# SuperClock_LED.net
KiCad netlist of a schematic drawn in Altium Designer
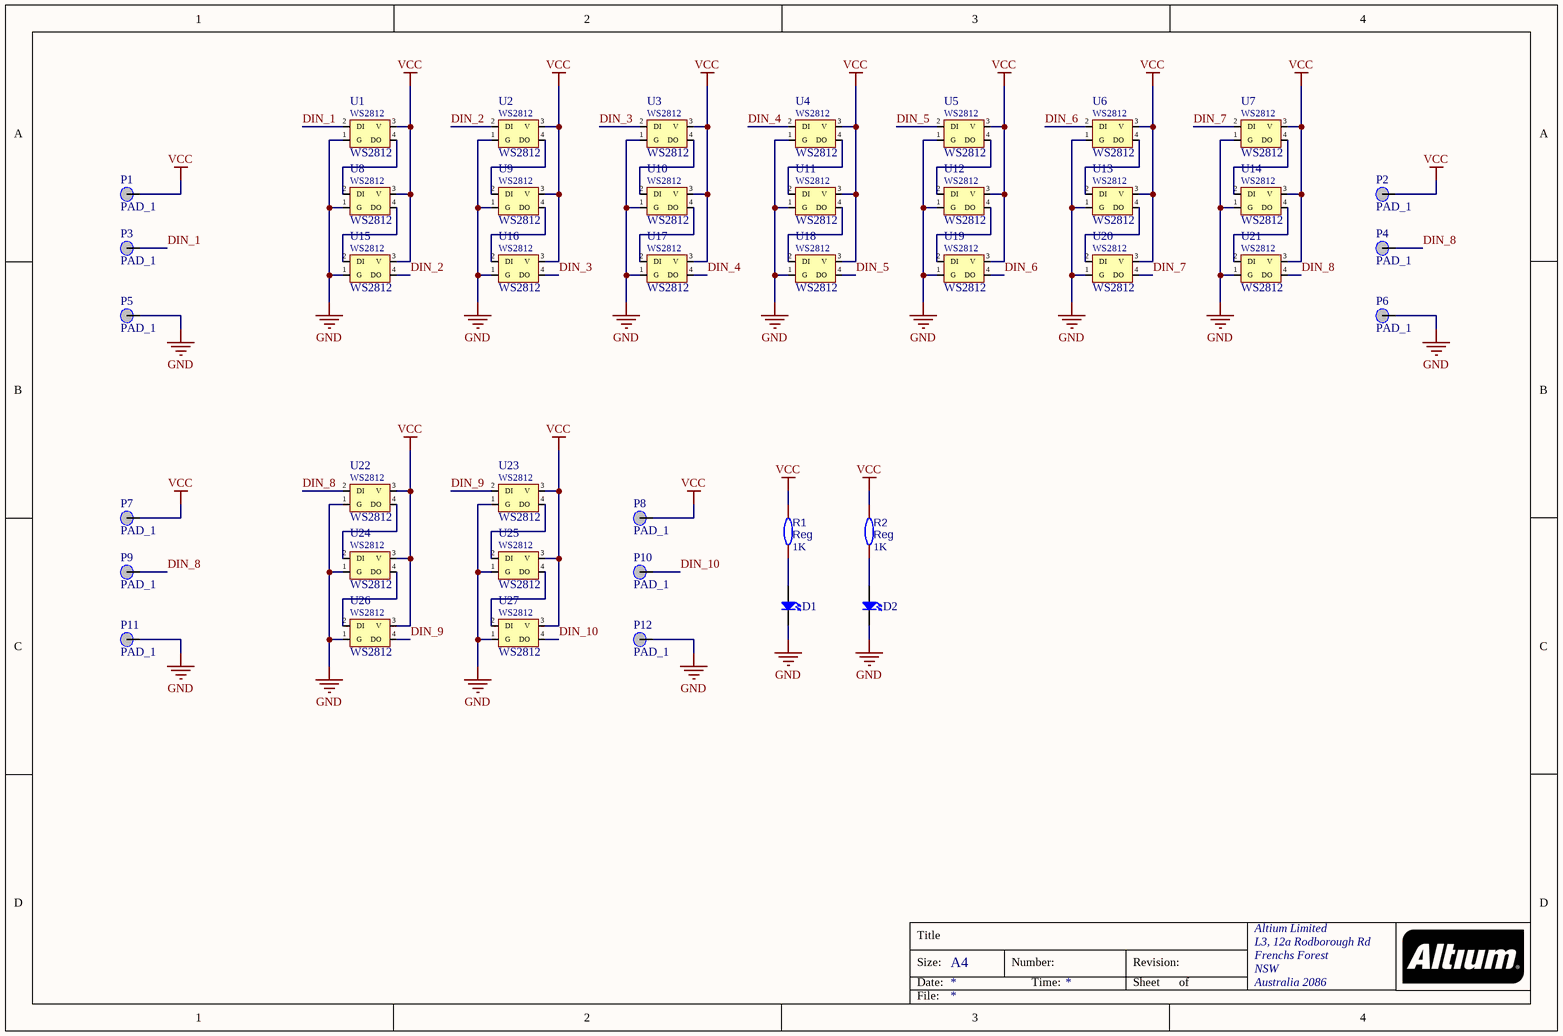
[diagram p0: SuperClock_LED.SchDoc]

(export (version "E")
  (design (tool "Eeschema 10.0.6"))
  (components
    (comp (ref "D1")
      (value "LED")
      (footprint "LED0603")
      (fields (field (name "PUBLISHER") "Altium Limited"))
      (libsource (lib "Levent_lib") (part "LED0"))
    )
    (comp (ref "D2")
      (value "LED")
      (footprint "LED0603")
      (fields (field (name "PUBLISHER") "Altium Limited"))
      (libsource (lib "Levent_lib") (part "LED0"))
    )
    (comp (ref "P1")
      (value "PAD_1")
      (footprint "PAD_PIN_1_SMD_ARC")
      (description "1脚焊盘")
      (libsource (lib "Levent_lib") (part "PAD_1"))
    )
    (comp (ref "P2")
      (value "PAD_1")
      (footprint "PAD_PIN_1_SMD_ARC")
      (description "1脚焊盘")
      (libsource (lib "Levent_lib") (part "PAD_1"))
    )
    (comp (ref "P3")
      (value "PAD_1")
      (footprint "PAD_PIN_1_SMD_ARC")
      (description "1脚焊盘")
      (libsource (lib "Levent_lib") (part "PAD_1"))
    )
    (comp (ref "P4")
      (value "PAD_1")
      (footprint "PAD_PIN_1_SMD_ARC")
      (description "1脚焊盘")
      (libsource (lib "Levent_lib") (part "PAD_1"))
    )
    (comp (ref "P5")
      (value "PAD_1")
      (footprint "PAD_PIN_1_SMD_ARC")
      (description "1脚焊盘")
      (libsource (lib "Levent_lib") (part "PAD_1"))
    )
    (comp (ref "P6")
      (value "PAD_1")
      (footprint "PAD_PIN_1_SMD_ARC")
      (description "1脚焊盘")
      (libsource (lib "Levent_lib") (part "PAD_1"))
    )
    (comp (ref "P7")
      (value "PAD_1")
      (footprint "PAD_PIN_1_SMD_ARC")
      (description "1脚焊盘")
      (libsource (lib "Levent_lib") (part "PAD_1"))
    )
    (comp (ref "P8")
      (value "PAD_1")
      (footprint "PAD_PIN_1_SMD_ARC")
      (description "1脚焊盘")
      (libsource (lib "Levent_lib") (part "PAD_1"))
    )
    (comp (ref "P9")
      (value "PAD_1")
      (footprint "PAD_PIN_1_SMD_ARC")
      (description "1脚焊盘")
      (libsource (lib "Levent_lib") (part "PAD_1"))
    )
    (comp (ref "P10")
      (value "PAD_1")
      (footprint "PAD_PIN_1_SMD_ARC")
      (description "1脚焊盘")
      (libsource (lib "Levent_lib") (part "PAD_1"))
    )
    (comp (ref "P11")
      (value "PAD_1")
      (footprint "PAD_PIN_1_SMD_ARC")
      (description "1脚焊盘")
      (libsource (lib "Levent_lib") (part "PAD_1"))
    )
    (comp (ref "P12")
      (value "PAD_1")
      (footprint "PAD_PIN_1_SMD_ARC")
      (description "1脚焊盘")
      (libsource (lib "Levent_lib") (part "PAD_1"))
    )
    (comp (ref "R1")
      (value "Reg")
      (footprint "R0603")
      (description "电阻")
      (fields
        (field (name "BOM_SUPPLIER PART") "C465721")
        (field (name "BOM_MANUFACTURER PART") "AR03BTCX1002A")
        (field (name "ALTIUM_VALUE") "1K")
        (field (name "CONTRIBUTOR") "LCSC")
      )
      (libsource (lib "Levent_lib") (part "Res"))
    )
    (comp (ref "R2")
      (value "Reg")
      (footprint "R0603")
      (description "电阻")
      (fields
        (field (name "BOM_SUPPLIER PART") "C465721")
        (field (name "BOM_MANUFACTURER PART") "AR03BTCX1002A")
        (field (name "ALTIUM_VALUE") "1K")
        (field (name "CONTRIBUTOR") "LCSC")
      )
      (libsource (lib "Levent_lib") (part "Res"))
    )
    (comp (ref "U1")
      (value "WS2812")
      (footprint "WS2812B-2020")
      (description "WS2812全色LED")
      (libsource (lib "Levent_lib") (part "WS2812"))
    )
    (comp (ref "U2")
      (value "WS2812")
      (footprint "WS2812B-2020")
      (description "WS2812全色LED")
      (libsource (lib "Levent_lib") (part "WS2812"))
    )
    (comp (ref "U3")
      (value "WS2812")
      (footprint "WS2812B-2020")
      (description "WS2812全色LED")
      (libsource (lib "Levent_lib") (part "WS2812"))
    )
    (comp (ref "U4")
      (value "WS2812")
      (footprint "WS2812B-2020")
      (description "WS2812全色LED")
      (libsource (lib "Levent_lib") (part "WS2812"))
    )
    (comp (ref "U5")
      (value "WS2812")
      (footprint "WS2812B-2020")
      (description "WS2812全色LED")
      (libsource (lib "Levent_lib") (part "WS2812"))
    )
    (comp (ref "U6")
      (value "WS2812")
      (footprint "WS2812B-2020")
      (description "WS2812全色LED")
      (libsource (lib "Levent_lib") (part "WS2812"))
    )
    (comp (ref "U7")
      (value "WS2812")
      (footprint "WS2812B-2020")
      (description "WS2812全色LED")
      (libsource (lib "Levent_lib") (part "WS2812"))
    )
    (comp (ref "U8")
      (value "WS2812")
      (footprint "WS2812B-2020")
      (description "WS2812全色LED")
      (libsource (lib "Levent_lib") (part "WS2812"))
    )
    (comp (ref "U9")
      (value "WS2812")
      (footprint "WS2812B-2020")
      (description "WS2812全色LED")
      (libsource (lib "Levent_lib") (part "WS2812"))
    )
    (comp (ref "U10")
      (value "WS2812")
      (footprint "WS2812B-2020")
      (description "WS2812全色LED")
      (libsource (lib "Levent_lib") (part "WS2812"))
    )
    (comp (ref "U11")
      (value "WS2812")
      (footprint "WS2812B-2020")
      (description "WS2812全色LED")
      (libsource (lib "Levent_lib") (part "WS2812"))
    )
    (comp (ref "U12")
      (value "WS2812")
      (footprint "WS2812B-2020")
      (description "WS2812全色LED")
      (libsource (lib "Levent_lib") (part "WS2812"))
    )
    (comp (ref "U13")
      (value "WS2812")
      (footprint "WS2812B-2020")
      (description "WS2812全色LED")
      (libsource (lib "Levent_lib") (part "WS2812"))
    )
    (comp (ref "U14")
      (value "WS2812")
      (footprint "WS2812B-2020")
      (description "WS2812全色LED")
      (libsource (lib "Levent_lib") (part "WS2812"))
    )
    (comp (ref "U15")
      (value "WS2812")
      (footprint "WS2812B-2020")
      (description "WS2812全色LED")
      (libsource (lib "Levent_lib") (part "WS2812"))
    )
    (comp (ref "U16")
      (value "WS2812")
      (footprint "WS2812B-2020")
      (description "WS2812全色LED")
      (libsource (lib "Levent_lib") (part "WS2812"))
    )
    (comp (ref "U17")
      (value "WS2812")
      (footprint "WS2812B-2020")
      (description "WS2812全色LED")
      (libsource (lib "Levent_lib") (part "WS2812"))
    )
    (comp (ref "U18")
      (value "WS2812")
      (footprint "WS2812B-2020")
      (description "WS2812全色LED")
      (libsource (lib "Levent_lib") (part "WS2812"))
    )
    (comp (ref "U19")
      (value "WS2812")
      (footprint "WS2812B-2020")
      (description "WS2812全色LED")
      (libsource (lib "Levent_lib") (part "WS2812"))
    )
    (comp (ref "U20")
      (value "WS2812")
      (footprint "WS2812B-2020")
      (description "WS2812全色LED")
      (libsource (lib "Levent_lib") (part "WS2812"))
    )
    (comp (ref "U21")
      (value "WS2812")
      (footprint "WS2812B-2020")
      (description "WS2812全色LED")
      (libsource (lib "Levent_lib") (part "WS2812"))
    )
    (comp (ref "U22")
      (value "WS2812")
      (footprint "WS2812B-2020")
      (description "WS2812全色LED")
      (libsource (lib "Levent_lib") (part "WS2812"))
    )
    (comp (ref "U23")
      (value "WS2812")
      (footprint "WS2812B-2020")
      (description "WS2812全色LED")
      (libsource (lib "Levent_lib") (part "WS2812"))
    )
    (comp (ref "U24")
      (value "WS2812")
      (footprint "WS2812B-2020")
      (description "WS2812全色LED")
      (libsource (lib "Levent_lib") (part "WS2812"))
    )
    (comp (ref "U25")
      (value "WS2812")
      (footprint "WS2812B-2020")
      (description "WS2812全色LED")
      (libsource (lib "Levent_lib") (part "WS2812"))
    )
    (comp (ref "U26")
      (value "WS2812")
      (footprint "WS2812B-2020")
      (description "WS2812全色LED")
      (libsource (lib "Levent_lib") (part "WS2812"))
    )
    (comp (ref "U27")
      (value "WS2812")
      (footprint "WS2812B-2020")
      (description "WS2812全色LED")
      (libsource (lib "Levent_lib") (part "WS2812"))
    )
  )
  (nets
    (net (code "1") (name "/DIN_1") (class "Default")
      (node (ref "P3") (pin "1") (pinfunction "1_1") (pintype "passive"))
      (node (ref "U1") (pin "2") (pinfunction "DI_2") (pintype "passive"))
    )
    (net (code "2") (name "/DIN_2") (class "Default")
      (node (ref "U15") (pin "4") (pinfunction "DO_4") (pintype "passive"))
      (node (ref "U2") (pin "2") (pinfunction "DI_2") (pintype "passive"))
    )
    (net (code "3") (name "/DIN_3") (class "Default")
      (node (ref "U16") (pin "4") (pinfunction "DO_4") (pintype "passive"))
      (node (ref "U3") (pin "2") (pinfunction "DI_2") (pintype "passive"))
    )
    (net (code "4") (name "/DIN_4") (class "Default")
      (node (ref "U17") (pin "4") (pinfunction "DO_4") (pintype "passive"))
      (node (ref "U4") (pin "2") (pinfunction "DI_2") (pintype "passive"))
    )
    (net (code "5") (name "/DIN_5") (class "Default")
      (node (ref "U18") (pin "4") (pinfunction "DO_4") (pintype "passive"))
      (node (ref "U5") (pin "2") (pinfunction "DI_2") (pintype "passive"))
    )
    (net (code "6") (name "/DIN_6") (class "Default")
      (node (ref "U19") (pin "4") (pinfunction "DO_4") (pintype "passive"))
      (node (ref "U6") (pin "2") (pinfunction "DI_2") (pintype "passive"))
    )
    (net (code "7") (name "/DIN_7") (class "Default")
      (node (ref "U20") (pin "4") (pinfunction "DO_4") (pintype "passive"))
      (node (ref "U7") (pin "2") (pinfunction "DI_2") (pintype "passive"))
    )
    (net (code "8") (name "/DIN_8") (class "Default")
      (node (ref "P4") (pin "1") (pinfunction "1_1") (pintype "passive"))
      (node (ref "P9") (pin "1") (pinfunction "1_1") (pintype "passive"))
      (node (ref "U21") (pin "4") (pinfunction "DO_4") (pintype "passive"))
      (node (ref "U22") (pin "2") (pinfunction "DI_2") (pintype "passive"))
    )
    (net (code "9") (name "/DIN_9") (class "Default")
      (node (ref "U23") (pin "2") (pinfunction "DI_2") (pintype "passive"))
      (node (ref "U26") (pin "4") (pinfunction "DO_4") (pintype "passive"))
    )
    (net (code "10") (name "/DIN_10") (class "Default")
      (node (ref "P10") (pin "1") (pinfunction "1_1") (pintype "passive"))
      (node (ref "U27") (pin "4") (pinfunction "DO_4") (pintype "passive"))
    )
    (net (code "11") (name "GND") (class "Default")
      (node (ref "D1") (pin "1") (pinfunction "K_1") (pintype "passive"))
      (node (ref "D2") (pin "1") (pinfunction "K_1") (pintype "passive"))
      (node (ref "P11") (pin "1") (pinfunction "1_1") (pintype "passive"))
      (node (ref "P12") (pin "1") (pinfunction "1_1") (pintype "passive"))
      (node (ref "P5") (pin "1") (pinfunction "1_1") (pintype "passive"))
      (node (ref "P6") (pin "1") (pinfunction "1_1") (pintype "passive"))
      (node (ref "U1") (pin "1") (pinfunction "G_1") (pintype "passive"))
      (node (ref "U10") (pin "1") (pinfunction "G_1") (pintype "passive"))
      (node (ref "U11") (pin "1") (pinfunction "G_1") (pintype "passive"))
      (node (ref "U12") (pin "1") (pinfunction "G_1") (pintype "passive"))
      (node (ref "U13") (pin "1") (pinfunction "G_1") (pintype "passive"))
      (node (ref "U14") (pin "1") (pinfunction "G_1") (pintype "passive"))
      (node (ref "U15") (pin "1") (pinfunction "G_1") (pintype "passive"))
      (node (ref "U16") (pin "1") (pinfunction "G_1") (pintype "passive"))
      (node (ref "U17") (pin "1") (pinfunction "G_1") (pintype "passive"))
      (node (ref "U18") (pin "1") (pinfunction "G_1") (pintype "passive"))
      (node (ref "U19") (pin "1") (pinfunction "G_1") (pintype "passive"))
      (node (ref "U2") (pin "1") (pinfunction "G_1") (pintype "passive"))
      (node (ref "U20") (pin "1") (pinfunction "G_1") (pintype "passive"))
      (node (ref "U21") (pin "1") (pinfunction "G_1") (pintype "passive"))
      (node (ref "U22") (pin "1") (pinfunction "G_1") (pintype "passive"))
      (node (ref "U23") (pin "1") (pinfunction "G_1") (pintype "passive"))
      (node (ref "U24") (pin "1") (pinfunction "G_1") (pintype "passive"))
      (node (ref "U25") (pin "1") (pinfunction "G_1") (pintype "passive"))
      (node (ref "U26") (pin "1") (pinfunction "G_1") (pintype "passive"))
      (node (ref "U27") (pin "1") (pinfunction "G_1") (pintype "passive"))
      (node (ref "U3") (pin "1") (pinfunction "G_1") (pintype "passive"))
      (node (ref "U4") (pin "1") (pinfunction "G_1") (pintype "passive"))
      (node (ref "U5") (pin "1") (pinfunction "G_1") (pintype "passive"))
      (node (ref "U6") (pin "1") (pinfunction "G_1") (pintype "passive"))
      (node (ref "U7") (pin "1") (pinfunction "G_1") (pintype "passive"))
      (node (ref "U8") (pin "1") (pinfunction "G_1") (pintype "passive"))
      (node (ref "U9") (pin "1") (pinfunction "G_1") (pintype "passive"))
    )
    (net (code "12") (name "Net-(D1-A)") (class "Default")
      (node (ref "D1") (pin "2") (pinfunction "A_2") (pintype "passive"))
      (node (ref "R1") (pin "1") (pinfunction "1_1") (pintype "passive"))
    )
    (net (code "13") (name "Net-(D2-A)") (class "Default")
      (node (ref "D2") (pin "2") (pinfunction "A_2") (pintype "passive"))
      (node (ref "R2") (pin "1") (pinfunction "1_1") (pintype "passive"))
    )
    (net (code "14") (name "Net-(U1-DO)") (class "Default")
      (node (ref "U1") (pin "4") (pinfunction "DO_4") (pintype "passive"))
      (node (ref "U8") (pin "2") (pinfunction "DI_2") (pintype "passive"))
    )
    (net (code "15") (name "Net-(U2-DO)") (class "Default")
      (node (ref "U2") (pin "4") (pinfunction "DO_4") (pintype "passive"))
      (node (ref "U9") (pin "2") (pinfunction "DI_2") (pintype "passive"))
    )
    (net (code "16") (name "Net-(U10-DI)") (class "Default")
      (node (ref "U10") (pin "2") (pinfunction "DI_2") (pintype "passive"))
      (node (ref "U3") (pin "4") (pinfunction "DO_4") (pintype "passive"))
    )
    (net (code "17") (name "Net-(U10-DO)") (class "Default")
      (node (ref "U10") (pin "4") (pinfunction "DO_4") (pintype "passive"))
      (node (ref "U17") (pin "2") (pinfunction "DI_2") (pintype "passive"))
    )
    (net (code "18") (name "Net-(U11-DI)") (class "Default")
      (node (ref "U11") (pin "2") (pinfunction "DI_2") (pintype "passive"))
      (node (ref "U4") (pin "4") (pinfunction "DO_4") (pintype "passive"))
    )
    (net (code "19") (name "Net-(U11-DO)") (class "Default")
      (node (ref "U11") (pin "4") (pinfunction "DO_4") (pintype "passive"))
      (node (ref "U18") (pin "2") (pinfunction "DI_2") (pintype "passive"))
    )
    (net (code "20") (name "Net-(U12-DI)") (class "Default")
      (node (ref "U12") (pin "2") (pinfunction "DI_2") (pintype "passive"))
      (node (ref "U5") (pin "4") (pinfunction "DO_4") (pintype "passive"))
    )
    (net (code "21") (name "Net-(U12-DO)") (class "Default")
      (node (ref "U12") (pin "4") (pinfunction "DO_4") (pintype "passive"))
      (node (ref "U19") (pin "2") (pinfunction "DI_2") (pintype "passive"))
    )
    (net (code "22") (name "Net-(U13-DI)") (class "Default")
      (node (ref "U13") (pin "2") (pinfunction "DI_2") (pintype "passive"))
      (node (ref "U6") (pin "4") (pinfunction "DO_4") (pintype "passive"))
    )
    (net (code "23") (name "Net-(U13-DO)") (class "Default")
      (node (ref "U13") (pin "4") (pinfunction "DO_4") (pintype "passive"))
      (node (ref "U20") (pin "2") (pinfunction "DI_2") (pintype "passive"))
    )
    (net (code "24") (name "Net-(U14-DI)") (class "Default")
      (node (ref "U14") (pin "2") (pinfunction "DI_2") (pintype "passive"))
      (node (ref "U7") (pin "4") (pinfunction "DO_4") (pintype "passive"))
    )
    (net (code "25") (name "Net-(U14-DO)") (class "Default")
      (node (ref "U14") (pin "4") (pinfunction "DO_4") (pintype "passive"))
      (node (ref "U21") (pin "2") (pinfunction "DI_2") (pintype "passive"))
    )
    (net (code "26") (name "Net-(U15-DI)") (class "Default")
      (node (ref "U15") (pin "2") (pinfunction "DI_2") (pintype "passive"))
      (node (ref "U8") (pin "4") (pinfunction "DO_4") (pintype "passive"))
    )
    (net (code "27") (name "Net-(U16-DI)") (class "Default")
      (node (ref "U16") (pin "2") (pinfunction "DI_2") (pintype "passive"))
      (node (ref "U9") (pin "4") (pinfunction "DO_4") (pintype "passive"))
    )
    (net (code "28") (name "Net-(U22-DO)") (class "Default")
      (node (ref "U22") (pin "4") (pinfunction "DO_4") (pintype "passive"))
      (node (ref "U24") (pin "2") (pinfunction "DI_2") (pintype "passive"))
    )
    (net (code "29") (name "Net-(U23-DO)") (class "Default")
      (node (ref "U23") (pin "4") (pinfunction "DO_4") (pintype "passive"))
      (node (ref "U25") (pin "2") (pinfunction "DI_2") (pintype "passive"))
    )
    (net (code "30") (name "Net-(U24-DO)") (class "Default")
      (node (ref "U24") (pin "4") (pinfunction "DO_4") (pintype "passive"))
      (node (ref "U26") (pin "2") (pinfunction "DI_2") (pintype "passive"))
    )
    (net (code "31") (name "Net-(U25-DO)") (class "Default")
      (node (ref "U25") (pin "4") (pinfunction "DO_4") (pintype "passive"))
      (node (ref "U27") (pin "2") (pinfunction "DI_2") (pintype "passive"))
    )
    (net (code "32") (name "VCC") (class "Default")
      (node (ref "P1") (pin "1") (pinfunction "1_1") (pintype "passive"))
      (node (ref "P2") (pin "1") (pinfunction "1_1") (pintype "passive"))
      (node (ref "P7") (pin "1") (pinfunction "1_1") (pintype "passive"))
      (node (ref "P8") (pin "1") (pinfunction "1_1") (pintype "passive"))
      (node (ref "R1") (pin "2") (pinfunction "2_2") (pintype "passive"))
      (node (ref "R2") (pin "2") (pinfunction "2_2") (pintype "passive"))
      (node (ref "U1") (pin "3") (pinfunction "V_3") (pintype "passive"))
      (node (ref "U10") (pin "3") (pinfunction "V_3") (pintype "passive"))
      (node (ref "U11") (pin "3") (pinfunction "V_3") (pintype "passive"))
      (node (ref "U12") (pin "3") (pinfunction "V_3") (pintype "passive"))
      (node (ref "U13") (pin "3") (pinfunction "V_3") (pintype "passive"))
      (node (ref "U14") (pin "3") (pinfunction "V_3") (pintype "passive"))
      (node (ref "U15") (pin "3") (pinfunction "V_3") (pintype "passive"))
      (node (ref "U16") (pin "3") (pinfunction "V_3") (pintype "passive"))
      (node (ref "U17") (pin "3") (pinfunction "V_3") (pintype "passive"))
      (node (ref "U18") (pin "3") (pinfunction "V_3") (pintype "passive"))
      (node (ref "U19") (pin "3") (pinfunction "V_3") (pintype "passive"))
      (node (ref "U2") (pin "3") (pinfunction "V_3") (pintype "passive"))
      (node (ref "U20") (pin "3") (pinfunction "V_3") (pintype "passive"))
      (node (ref "U21") (pin "3") (pinfunction "V_3") (pintype "passive"))
      (node (ref "U22") (pin "3") (pinfunction "V_3") (pintype "passive"))
      (node (ref "U23") (pin "3") (pinfunction "V_3") (pintype "passive"))
      (node (ref "U24") (pin "3") (pinfunction "V_3") (pintype "passive"))
      (node (ref "U25") (pin "3") (pinfunction "V_3") (pintype "passive"))
      (node (ref "U26") (pin "3") (pinfunction "V_3") (pintype "passive"))
      (node (ref "U27") (pin "3") (pinfunction "V_3") (pintype "passive"))
      (node (ref "U3") (pin "3") (pinfunction "V_3") (pintype "passive"))
      (node (ref "U4") (pin "3") (pinfunction "V_3") (pintype "passive"))
      (node (ref "U5") (pin "3") (pinfunction "V_3") (pintype "passive"))
      (node (ref "U6") (pin "3") (pinfunction "V_3") (pintype "passive"))
      (node (ref "U7") (pin "3") (pinfunction "V_3") (pintype "passive"))
      (node (ref "U8") (pin "3") (pinfunction "V_3") (pintype "passive"))
      (node (ref "U9") (pin "3") (pinfunction "V_3") (pintype "passive"))
    )
  )
)
